# RGB_Led_Controller.net
KiCad netlist of a schematic drawn in EAGLE
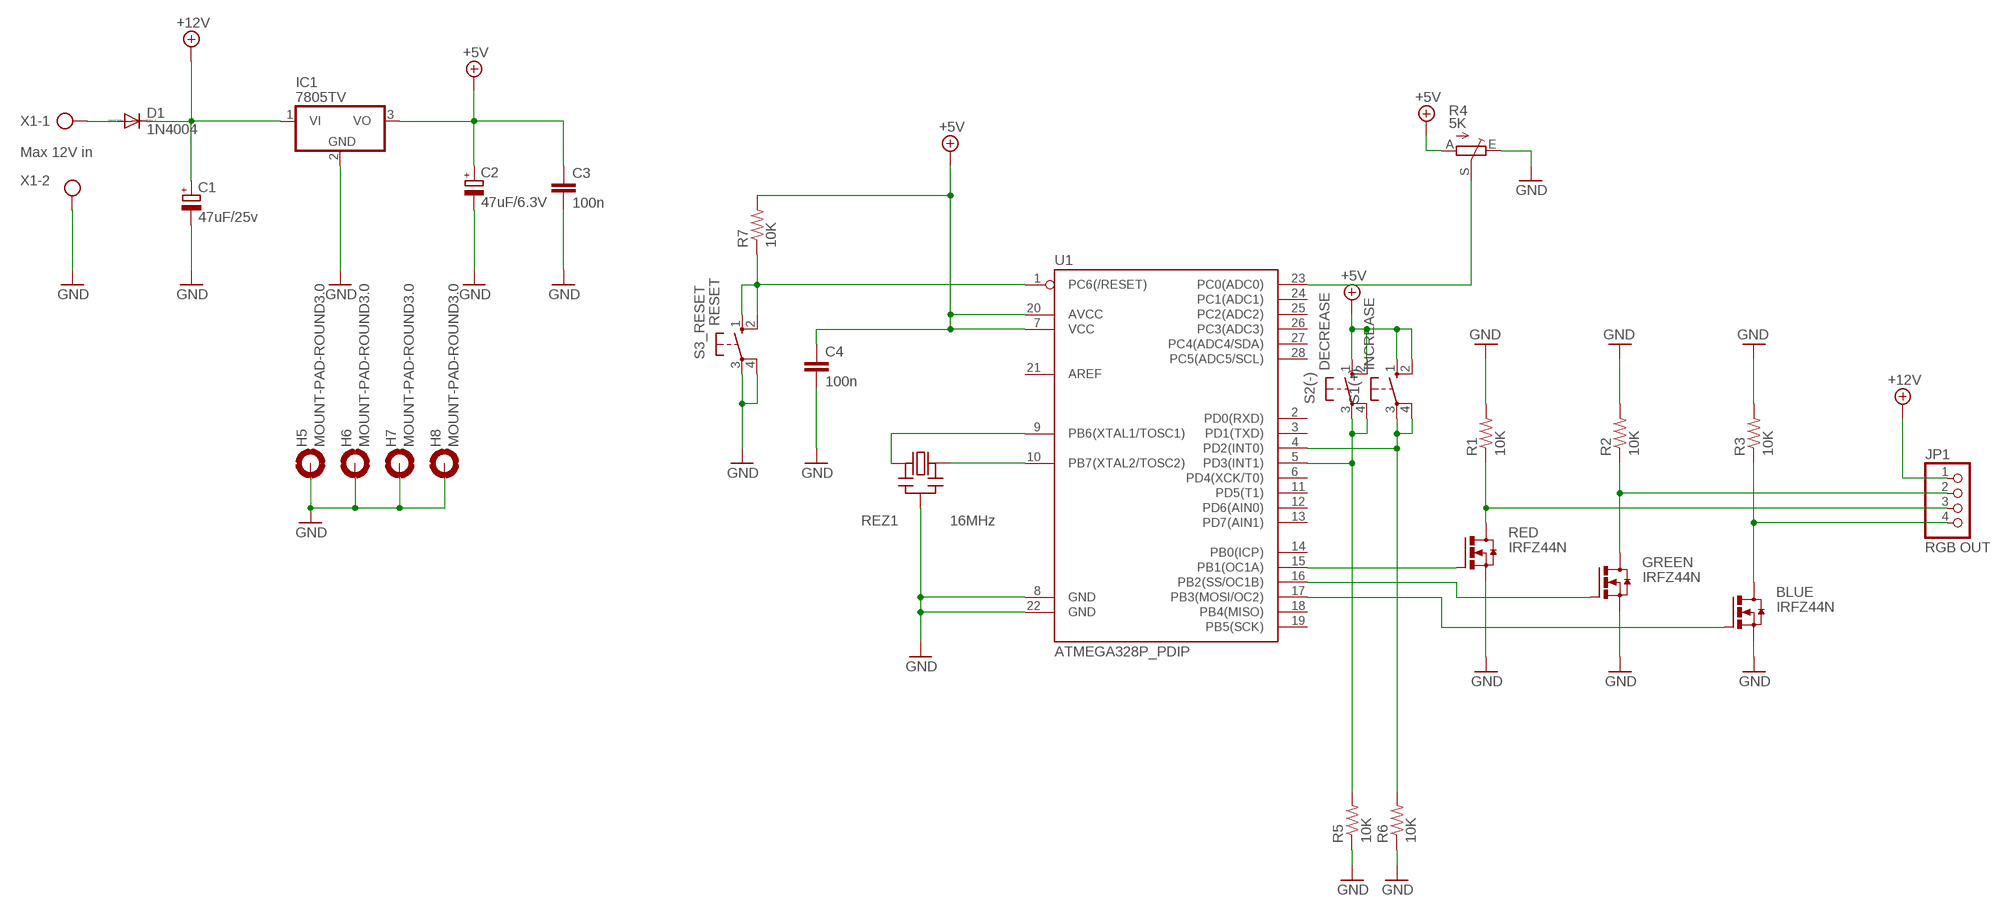
[diagram p0: schematic, sheet 1]

(export (version "E")
  (design (tool "Eeschema 10.0.6"))
  (components
    (comp (ref "BLUE")
      (value "IRFZ44N")
      (footprint "eagle-import:TO220V")
      (libsource (lib "eagle-import") (part "IRFZ44N"))
    )
    (comp (ref "C1")
      (value "47uF/25v")
      (footprint "eagle-import:E5-10,5")
      (libsource (lib "eagle-import") (part "CPOL-EUE5-10.5"))
    )
    (comp (ref "C2")
      (value "47uF/6.3V")
      (footprint "eagle-import:E5-10,5")
      (libsource (lib "eagle-import") (part "CPOL-EUE5-10.5"))
    )
    (comp (ref "C3")
      (value "100n")
      (footprint "eagle-import:CAP-PTH-SMALLEZ")
      (libsource (lib "eagle-import") (part "CAPEZ"))
    )
    (comp (ref "C4")
      (value "100n")
      (footprint "eagle-import:CAP-PTH-SMALLEZ")
      (libsource (lib "eagle-import") (part "CAPEZ"))
    )
    (comp (ref "D1")
      (value "1N4004")
      (footprint "eagle-import:DO41-10")
      (libsource (lib "eagle-import") (part "1N4004"))
    )
    (comp (ref "GREEN")
      (value "IRFZ44N")
      (footprint "eagle-import:TO220V")
      (libsource (lib "eagle-import") (part "IRFZ44N"))
    )
    (comp (ref "H5")
      (value "MOUNT-PAD-ROUND3.0")
      (footprint "eagle-import:3,0-PAD")
      (libsource (lib "eagle-import") (part "MOUNT-PAD-ROUND3.0"))
    )
    (comp (ref "H6")
      (value "MOUNT-PAD-ROUND3.0")
      (footprint "eagle-import:3,0-PAD")
      (libsource (lib "eagle-import") (part "MOUNT-PAD-ROUND3.0"))
    )
    (comp (ref "H7")
      (value "MOUNT-PAD-ROUND3.0")
      (footprint "eagle-import:3,0-PAD")
      (libsource (lib "eagle-import") (part "MOUNT-PAD-ROUND3.0"))
    )
    (comp (ref "H8")
      (value "MOUNT-PAD-ROUND3.0")
      (footprint "eagle-import:3,0-PAD")
      (libsource (lib "eagle-import") (part "MOUNT-PAD-ROUND3.0"))
    )
    (comp (ref "IC1")
      (value "7805TV")
      (footprint "eagle-import:TO220V")
      (libsource (lib "eagle-import") (part "78TV05"))
    )
    (comp (ref "JP1")
      (value "RGB OUT")
      (footprint "eagle-import:1X04")
      (libsource (lib "eagle-import") (part "PINHD-1X4"))
    )
    (comp (ref "R1")
      (value "10K")
      (footprint "eagle-import:0309_12")
      (libsource (lib "eagle-import") (part "R-US_0309/12"))
    )
    (comp (ref "R2")
      (value "10K")
      (footprint "eagle-import:0309_12")
      (libsource (lib "eagle-import") (part "R-US_0309/12"))
    )
    (comp (ref "R3")
      (value "10K")
      (footprint "eagle-import:0309_12")
      (libsource (lib "eagle-import") (part "R-US_0309/12"))
    )
    (comp (ref "R4")
      (value "5K")
      (footprint "eagle-import:CIP20C-6MM")
      (libsource (lib "eagle-import") (part "TRIM_EU-CIP20C-6MM"))
    )
    (comp (ref "R5")
      (value "10K")
      (footprint "eagle-import:0309_12")
      (libsource (lib "eagle-import") (part "R-US_0309/12"))
    )
    (comp (ref "R6")
      (value "10K")
      (footprint "eagle-import:0309_12")
      (libsource (lib "eagle-import") (part "R-US_0309/12"))
    )
    (comp (ref "R7")
      (value "10K")
      (footprint "eagle-import:0309_12")
      (libsource (lib "eagle-import") (part "R-US_0309/12"))
    )
    (comp (ref "RED")
      (value "IRFZ44N")
      (footprint "eagle-import:TO220V")
      (libsource (lib "eagle-import") (part "IRFZ44N"))
    )
    (comp (ref "REZ1")
      (value "16MHz")
      (footprint "eagle-import:CERM_OSC")
      (libsource (lib "eagle-import") (part "CERMOSCILL-THM"))
    )
    (comp (ref "S1(+)")
      (value "INCREASE")
      (footprint "eagle-import:B3F-10XX")
      (fields (field (name "MPN") "B3F-1000"))
      (libsource (lib "eagle-import") (part "10-XX"))
    )
    (comp (ref "S2(-)")
      (value "DECREASE")
      (footprint "eagle-import:B3F-10XX")
      (fields (field (name "MPN") "B3F-1000"))
      (libsource (lib "eagle-import") (part "10-XX"))
    )
    (comp (ref "S3_RESET")
      (value "RESET")
      (footprint "eagle-import:B3F-10XX")
      (fields (field (name "MPN") "B3F-1000"))
      (libsource (lib "eagle-import") (part "10-XX"))
    )
    (comp (ref "U1")
      (value "ATMEGA328P_PDIP")
      (footprint "eagle-import:DIL28-3")
      (libsource (lib "eagle-import") (part "ATMEGA328P_PDIP"))
    )
    (comp (ref "X1")
      (value "Max 12V in")
      (footprint "eagle-import:AK300_2")
      (libsource (lib "eagle-import") (part "AK300/2"))
    )
  )
  (nets
    (net (code "1") (name "+5V") (class "Default")
      (node (ref "C2") (pin "+") (pinfunction "+_+") (pintype "passive"))
      (node (ref "C3") (pin "1") (pinfunction "1_1") (pintype "passive"))
      (node (ref "C4") (pin "1") (pinfunction "1_1") (pintype "passive"))
      (node (ref "IC1") (pin "3") (pinfunction "VO_3") (pintype "passive"))
      (node (ref "R4") (pin "A") (pinfunction "A_A") (pintype "passive"))
      (node (ref "R7") (pin "2") (pinfunction "2_2") (pintype "passive"))
      (node (ref "S1(+)") (pin "1") (pinfunction "S_1") (pintype "passive"))
      (node (ref "S1(+)") (pin "2") (pinfunction "S1_2") (pintype "passive"))
      (node (ref "S2(-)") (pin "1") (pinfunction "S_1") (pintype "passive"))
      (node (ref "S2(-)") (pin "2") (pinfunction "S1_2") (pintype "passive"))
      (node (ref "U1") (pin "20") (pinfunction "AVCC_20") (pintype "bidirectional"))
      (node (ref "U1") (pin "7") (pinfunction "VCC_7") (pintype "bidirectional"))
    )
    (net (code "2") (name "+12V") (class "Default")
      (node (ref "C1") (pin "+") (pinfunction "+_+") (pintype "passive"))
      (node (ref "D1") (pin "C") (pinfunction "C_C") (pintype "passive"))
      (node (ref "IC1") (pin "1") (pinfunction "VI_1") (pintype "input"))
      (node (ref "JP1") (pin "1") (pinfunction "1_1") (pintype "passive"))
    )
    (net (code "3") (name "GND") (class "Default")
      (node (ref "BLUE") (pin "3") (pinfunction "S_3") (pintype "passive"))
      (node (ref "C1") (pin "-") (pinfunction "-_-") (pintype "passive"))
      (node (ref "C2") (pin "-") (pinfunction "-_-") (pintype "passive"))
      (node (ref "C3") (pin "2") (pinfunction "2_2") (pintype "passive"))
      (node (ref "C4") (pin "2") (pinfunction "2_2") (pintype "passive"))
      (node (ref "GREEN") (pin "3") (pinfunction "S_3") (pintype "passive"))
      (node (ref "H5") (pin "B3,0") (pinfunction "MOUNT_B3,0") (pintype "passive"))
      (node (ref "H6") (pin "B3,0") (pinfunction "MOUNT_B3,0") (pintype "passive"))
      (node (ref "H7") (pin "B3,0") (pinfunction "MOUNT_B3,0") (pintype "passive"))
      (node (ref "H8") (pin "B3,0") (pinfunction "MOUNT_B3,0") (pintype "passive"))
      (node (ref "IC1") (pin "2") (pinfunction "GND_2") (pintype "passive"))
      (node (ref "R1") (pin "2") (pinfunction "2_2") (pintype "passive"))
      (node (ref "R2") (pin "2") (pinfunction "2_2") (pintype "passive"))
      (node (ref "R3") (pin "2") (pinfunction "2_2") (pintype "passive"))
      (node (ref "R4") (pin "E") (pinfunction "E_E") (pintype "passive"))
      (node (ref "R5") (pin "1") (pinfunction "1_1") (pintype "passive"))
      (node (ref "R6") (pin "1") (pinfunction "1_1") (pintype "passive"))
      (node (ref "RED") (pin "3") (pinfunction "S_3") (pintype "passive"))
      (node (ref "REZ1") (pin "P$2") (pinfunction "GND_P$2") (pintype "bidirectional"))
      (node (ref "S3_RESET") (pin "3") (pinfunction "P_3") (pintype "passive"))
      (node (ref "S3_RESET") (pin "4") (pinfunction "P1_4") (pintype "passive"))
      (node (ref "U1") (pin "22") (pinfunction "GND_22") (pintype "bidirectional"))
      (node (ref "U1") (pin "8") (pinfunction "GND_8") (pintype "bidirectional"))
      (node (ref "X1") (pin "2") (pinfunction "KL_2") (pintype "passive"))
    )
    (net (code "4") (name "Net-(BLUE-D)") (class "Default")
      (node (ref "BLUE") (pin "2") (pinfunction "D_2") (pintype "passive"))
      (node (ref "JP1") (pin "4") (pinfunction "4_4") (pintype "passive"))
      (node (ref "R3") (pin "1") (pinfunction "1_1") (pintype "passive"))
    )
    (net (code "5") (name "Net-(BLUE-G)") (class "Default")
      (node (ref "BLUE") (pin "1") (pinfunction "G_1") (pintype "passive"))
      (node (ref "U1") (pin "17") (pinfunction "PB3(MOSI/OC2)_17") (pintype "bidirectional"))
    )
    (net (code "6") (name "Net-(GREEN-D)") (class "Default")
      (node (ref "GREEN") (pin "2") (pinfunction "D_2") (pintype "passive"))
      (node (ref "JP1") (pin "2") (pinfunction "2_2") (pintype "passive"))
      (node (ref "R2") (pin "1") (pinfunction "1_1") (pintype "passive"))
    )
    (net (code "7") (name "Net-(GREEN-G)") (class "Default")
      (node (ref "GREEN") (pin "1") (pinfunction "G_1") (pintype "passive"))
      (node (ref "U1") (pin "16") (pinfunction "PB2(SS/OC1B)_16") (pintype "bidirectional"))
    )
    (net (code "8") (name "Net-(RED-D)") (class "Default")
      (node (ref "JP1") (pin "3") (pinfunction "3_3") (pintype "passive"))
      (node (ref "R1") (pin "1") (pinfunction "1_1") (pintype "passive"))
      (node (ref "RED") (pin "2") (pinfunction "D_2") (pintype "passive"))
    )
    (net (code "9") (name "Net-(RED-G)") (class "Default")
      (node (ref "RED") (pin "1") (pinfunction "G_1") (pintype "passive"))
      (node (ref "U1") (pin "15") (pinfunction "PB1(OC1A)_15") (pintype "bidirectional"))
    )
    (net (code "10") (name "Net-(REZ1-IN)") (class "Default")
      (node (ref "REZ1") (pin "P$1") (pinfunction "IN_P$1") (pintype "bidirectional"))
      (node (ref "U1") (pin "9") (pinfunction "PB6(XTAL1/TOSC1)_9") (pintype "bidirectional"))
    )
    (net (code "11") (name "Net-(REZ1-OUT)") (class "Default")
      (node (ref "REZ1") (pin "P$3") (pinfunction "OUT_P$3") (pintype "bidirectional"))
      (node (ref "U1") (pin "10") (pinfunction "PB7(XTAL2/TOSC2)_10") (pintype "bidirectional"))
    )
    (net (code "12") (name "Net-(S1(+)-P)") (class "Default")
      (node (ref "R6") (pin "2") (pinfunction "2_2") (pintype "passive"))
      (node (ref "S1(+)") (pin "3") (pinfunction "P_3") (pintype "passive"))
      (node (ref "S1(+)") (pin "4") (pinfunction "P1_4") (pintype "passive"))
      (node (ref "U1") (pin "4") (pinfunction "PD2(INT0)_4") (pintype "bidirectional"))
    )
    (net (code "13") (name "Net-(S2(-)-P)") (class "Default")
      (node (ref "R5") (pin "2") (pinfunction "2_2") (pintype "passive"))
      (node (ref "S2(-)") (pin "3") (pinfunction "P_3") (pintype "passive"))
      (node (ref "S2(-)") (pin "4") (pinfunction "P1_4") (pintype "passive"))
      (node (ref "U1") (pin "5") (pinfunction "PD3(INT1)_5") (pintype "bidirectional"))
    )
    (net (code "14") (name "Net-(S3_RESET-S)") (class "Default")
      (node (ref "R7") (pin "1") (pinfunction "1_1") (pintype "passive"))
      (node (ref "S3_RESET") (pin "1") (pinfunction "S_1") (pintype "passive"))
      (node (ref "S3_RESET") (pin "2") (pinfunction "S1_2") (pintype "passive"))
      (node (ref "U1") (pin "1") (pinfunction "PC6(/RESET)_1") (pintype "bidirectional"))
    )
    (net (code "15") (name "Net-(U1-PC0(ADC0))") (class "Default")
      (node (ref "R4") (pin "S") (pinfunction "S_S") (pintype "passive"))
      (node (ref "U1") (pin "23") (pinfunction "PC0(ADC0)_23") (pintype "bidirectional"))
    )
    (net (code "16") (name "Net-(X1A-KL)") (class "Default")
      (node (ref "D1") (pin "A") (pinfunction "A_A") (pintype "passive"))
      (node (ref "X1") (pin "1") (pinfunction "KL_1") (pintype "passive"))
    )
    (net (code "17") (name "unconnected-(U1-AREF-Pad21)") (class "Default")
      (node (ref "U1") (pin "21") (pinfunction "AREF_21") (pintype "bidirectional"))
    )
    (net (code "18") (name "unconnected-(U1-PB0(ICP)-Pad14)") (class "Default")
      (node (ref "U1") (pin "14") (pinfunction "PB0(ICP)_14") (pintype "bidirectional"))
    )
    (net (code "19") (name "unconnected-(U1-PB4(MISO)-Pad18)") (class "Default")
      (node (ref "U1") (pin "18") (pinfunction "PB4(MISO)_18") (pintype "bidirectional"))
    )
    (net (code "20") (name "unconnected-(U1-PB5(SCK)-Pad19)") (class "Default")
      (node (ref "U1") (pin "19") (pinfunction "PB5(SCK)_19") (pintype "bidirectional"))
    )
    (net (code "21") (name "unconnected-(U1-PC1(ADC1)-Pad24)") (class "Default")
      (node (ref "U1") (pin "24") (pinfunction "PC1(ADC1)_24") (pintype "bidirectional"))
    )
    (net (code "22") (name "unconnected-(U1-PC2(ADC2)-Pad25)") (class "Default")
      (node (ref "U1") (pin "25") (pinfunction "PC2(ADC2)_25") (pintype "bidirectional"))
    )
    (net (code "23") (name "unconnected-(U1-PC3(ADC3)-Pad26)") (class "Default")
      (node (ref "U1") (pin "26") (pinfunction "PC3(ADC3)_26") (pintype "bidirectional"))
    )
    (net (code "24") (name "unconnected-(U1-PC4(ADC4{slash}SDA)-Pad27)") (class "Default")
      (node (ref "U1") (pin "27") (pinfunction "PC4(ADC4/SDA)_27") (pintype "bidirectional"))
    )
    (net (code "25") (name "unconnected-(U1-PC5(ADC5{slash}SCL)-Pad28)") (class "Default")
      (node (ref "U1") (pin "28") (pinfunction "PC5(ADC5/SCL)_28") (pintype "bidirectional"))
    )
    (net (code "26") (name "unconnected-(U1-PD0(RXD)-Pad2)") (class "Default")
      (node (ref "U1") (pin "2") (pinfunction "PD0(RXD)_2") (pintype "bidirectional"))
    )
    (net (code "27") (name "unconnected-(U1-PD1(TXD)-Pad3)") (class "Default")
      (node (ref "U1") (pin "3") (pinfunction "PD1(TXD)_3") (pintype "bidirectional"))
    )
    (net (code "28") (name "unconnected-(U1-PD4(XCK{slash}T0)-Pad6)") (class "Default")
      (node (ref "U1") (pin "6") (pinfunction "PD4(XCK/T0)_6") (pintype "bidirectional"))
    )
    (net (code "29") (name "unconnected-(U1-PD5(T1)-Pad11)") (class "Default")
      (node (ref "U1") (pin "11") (pinfunction "PD5(T1)_11") (pintype "bidirectional"))
    )
    (net (code "30") (name "unconnected-(U1-PD6(AIN0)-Pad12)") (class "Default")
      (node (ref "U1") (pin "12") (pinfunction "PD6(AIN0)_12") (pintype "bidirectional"))
    )
    (net (code "31") (name "unconnected-(U1-PD7(AIN1)-Pad13)") (class "Default")
      (node (ref "U1") (pin "13") (pinfunction "PD7(AIN1)_13") (pintype "bidirectional"))
    )
  )
)
